# mcuPower.net
KiCad netlist of a schematic drawn in EAGLE
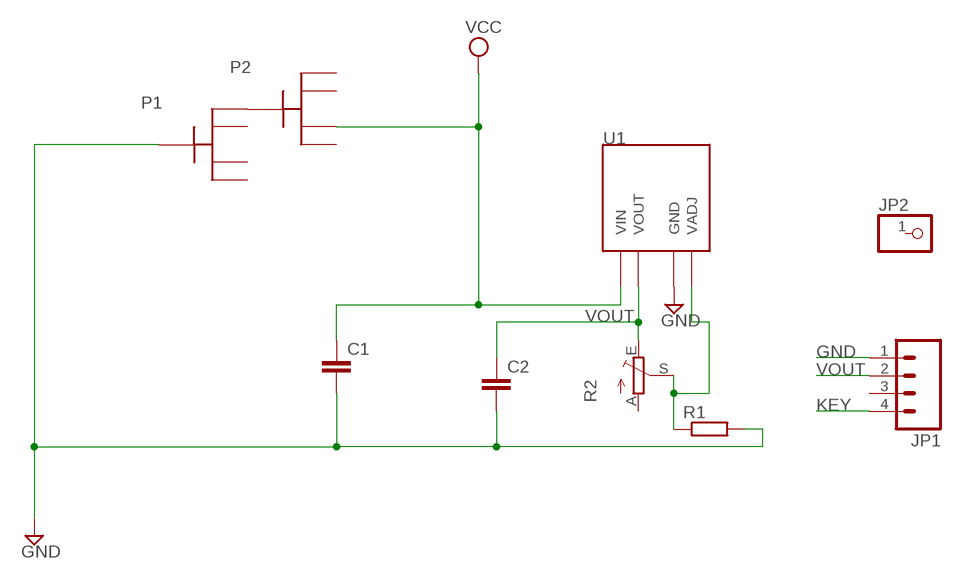
[diagram p0: schematic, sheet 1]

(export (version "E")
  (design (tool "Eeschema 10.0.6"))
  (components
    (comp (ref "C1")
      (value "C-EUC0805")
      (footprint "eagle-import:C0805")
      (libsource (lib "eagle-import") (part "C-EUC0805"))
    )
    (comp (ref "C2")
      (value "C-EUC0805")
      (footprint "eagle-import:C0805")
      (libsource (lib "eagle-import") (part "C-EUC0805"))
    )
    (comp (ref "JP1")
      (value "M04PTH")
      (footprint "eagle-import:1X04")
      (libsource (lib "eagle-import") (part "M04PTH"))
    )
    (comp (ref "JP2")
      (value "PINHD-1X1")
      (footprint "eagle-import:1X01")
      (libsource (lib "eagle-import") (part "PINHD-1X1"))
    )
    (comp (ref "P1")
      (value "CR2032")
      (footprint "eagle-import:CR2032_2025")
      (libsource (lib "eagle-import") (part "CR2032"))
    )
    (comp (ref "P2")
      (value "CR2032")
      (footprint "eagle-import:CR2032_2025")
      (libsource (lib "eagle-import") (part "CR2032"))
    )
    (comp (ref "R1")
      (value "R-EU_R0805")
      (footprint "eagle-import:R0805")
      (libsource (lib "eagle-import") (part "R-EU_R0805"))
    )
    (comp (ref "R2")
      (value "TRIM_EU-B25P")
      (footprint "eagle-import:B25P")
      (libsource (lib "eagle-import") (part "TRIM_EU-B25P"))
    )
    (comp (ref "U1")
      (value "PQ070XF01SZH")
      (footprint "eagle-import:TO220-4")
      (libsource (lib "eagle-import") (part "PQ070XF01SZH"))
    )
  )
  (nets
    (net (code "1") (name "/KEY") (class "Default")
      (node (ref "JP1") (pin "4") (pinfunction "4_4") (pintype "passive"))
    )
    (net (code "2") (name "/VOUT") (class "Default")
      (node (ref "C2") (pin "1") (pinfunction "1_1") (pintype "passive"))
      (node (ref "JP1") (pin "2") (pinfunction "2_2") (pintype "passive"))
      (node (ref "R2") (pin "E") (pinfunction "E_E") (pintype "passive"))
      (node (ref "U1") (pin "VOUT") (pinfunction "VOUT_VOUT") (pintype "bidirectional"))
    )
    (net (code "3") (name "GND") (class "Default")
      (node (ref "C1") (pin "2") (pinfunction "2_2") (pintype "passive"))
      (node (ref "C2") (pin "2") (pinfunction "2_2") (pintype "passive"))
      (node (ref "JP1") (pin "1") (pinfunction "1_1") (pintype "passive"))
      (node (ref "P1") (pin "GND") (pinfunction "GND_GND") (pintype "bidirectional"))
      (node (ref "R1") (pin "2") (pinfunction "2_2") (pintype "passive"))
      (node (ref "U1") (pin "GND") (pinfunction "GND_GND") (pintype "bidirectional"))
    )
    (net (code "4") (name "Net-(P1-PadVCC_1)") (class "Default")
      (node (ref "P1") (pin "VCC_1") (pinfunction "VCC_1_VCC_1") (pintype "bidirectional"))
      (node (ref "P2") (pin "GND") (pinfunction "GND_GND") (pintype "bidirectional"))
    )
    (net (code "5") (name "Net-(R1-Pad1)") (class "Default")
      (node (ref "R1") (pin "1") (pinfunction "1_1") (pintype "passive"))
      (node (ref "R2") (pin "S") (pinfunction "S_S") (pintype "passive"))
      (node (ref "U1") (pin "VADJ") (pinfunction "VADJ_VADJ") (pintype "bidirectional"))
    )
    (net (code "6") (name "VCC") (class "Default")
      (node (ref "C1") (pin "1") (pinfunction "1_1") (pintype "passive"))
      (node (ref "P2") (pin "VCC_3") (pinfunction "VCC_3_VCC_3") (pintype "bidirectional"))
      (node (ref "U1") (pin "VIN") (pinfunction "VIN_VIN") (pintype "bidirectional"))
    )
    (net (code "7") (name "unconnected-(JP1-Pad3)") (class "Default")
      (node (ref "JP1") (pin "3") (pinfunction "3_3") (pintype "passive"))
    )
    (net (code "8") (name "unconnected-(JP2-Pad1)") (class "Default")
      (node (ref "JP2") (pin "1") (pinfunction "1_1") (pintype "passive"))
    )
    (net (code "9") (name "unconnected-(P1-PadVCC_2)") (class "Default")
      (node (ref "P1") (pin "VCC_2") (pinfunction "VCC_2_VCC_2") (pintype "bidirectional"))
    )
    (net (code "10") (name "unconnected-(P1-PadVCC_3)") (class "Default")
      (node (ref "P1") (pin "VCC_3") (pinfunction "VCC_3_VCC_3") (pintype "bidirectional"))
    )
    (net (code "11") (name "unconnected-(P1-PadVCC_4)") (class "Default")
      (node (ref "P1") (pin "VCC_4") (pinfunction "VCC_4_VCC_4") (pintype "bidirectional"))
    )
    (net (code "12") (name "unconnected-(P2-PadVCC_1)") (class "Default")
      (node (ref "P2") (pin "VCC_1") (pinfunction "VCC_1_VCC_1") (pintype "bidirectional"))
    )
    (net (code "13") (name "unconnected-(P2-PadVCC_2)") (class "Default")
      (node (ref "P2") (pin "VCC_2") (pinfunction "VCC_2_VCC_2") (pintype "bidirectional"))
    )
    (net (code "14") (name "unconnected-(P2-PadVCC_4)") (class "Default")
      (node (ref "P2") (pin "VCC_4") (pinfunction "VCC_4_VCC_4") (pintype "bidirectional"))
    )
    (net (code "15") (name "unconnected-(R2-PadA)") (class "Default")
      (node (ref "R2") (pin "A") (pinfunction "A_A") (pintype "passive"))
    )
  )
)
